# 1LD-20-mk-1_0_0.net
KiCad netlist of a schematic drawn in EAGLE
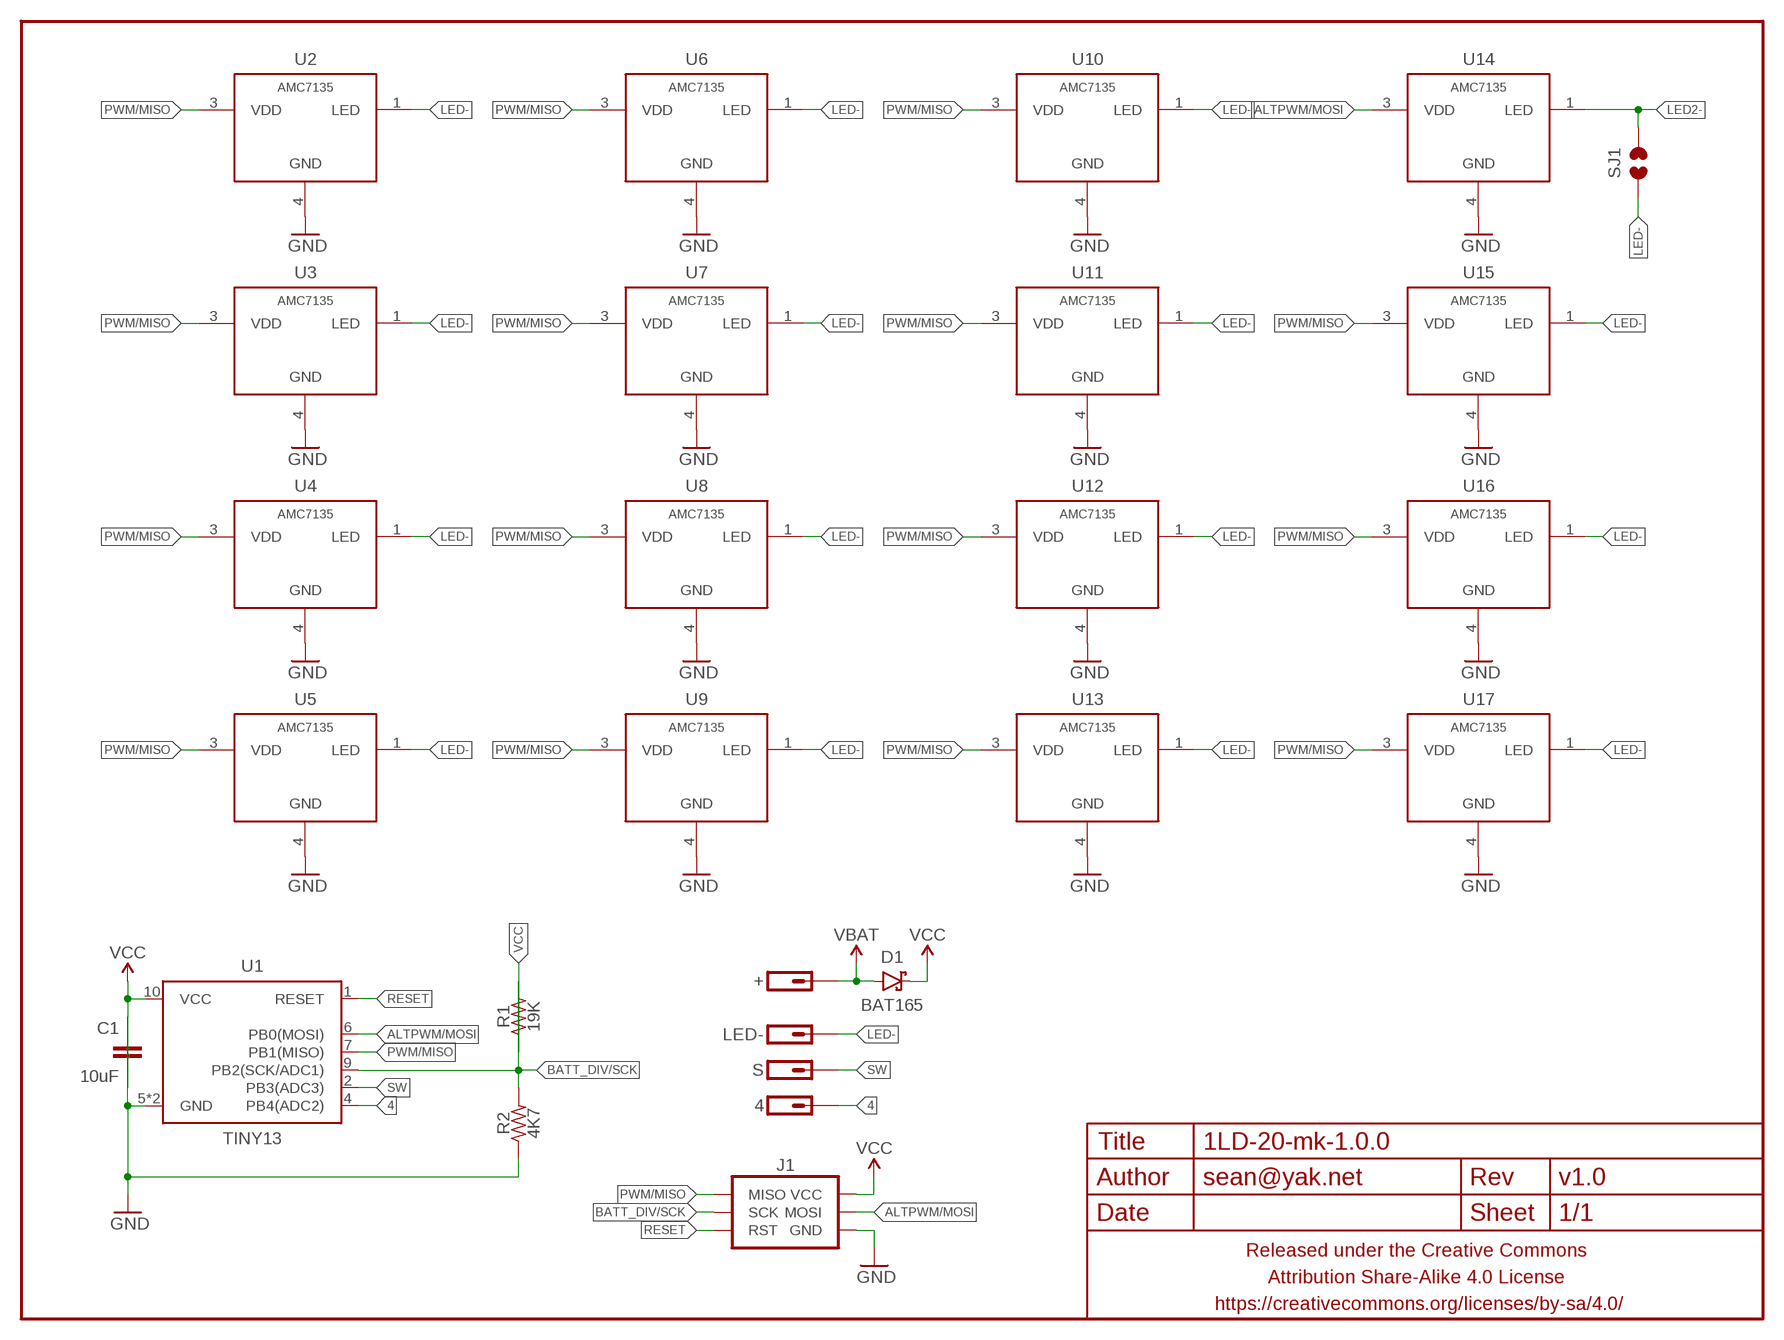
[diagram p0: schematic, sheet 1]

(export (version "E")
  (design (tool "Eeschema 10.0.6"))
  (components
    (comp (ref "+")
      (value "M01PTH-1.3MM-NARROWISH")
      (footprint "eagle-import:1X01-1.3MM-CIR-NARROW-NS")
      (libsource (lib "eagle-import") (part "M01PTH-1.3MM-NARROWISH"))
    )
    (comp (ref "4")
      (value "M01SMD-1MM-DIA-NS")
      (footprint "eagle-import:1X01-SMD-1MM-DIA-NS")
      (libsource (lib "eagle-import") (part "M01SMD-1MM-DIA-NS"))
    )
    (comp (ref "C1")
      (value "10uF")
      (footprint "eagle-import:C0402")
      (libsource (lib "eagle-import") (part "CAPACITOR-CERAMICC0402"))
    )
    (comp (ref "D1")
      (value "BAT165")
      (footprint "eagle-import:SOD323-SCHOTTKY")
      (libsource (lib "eagle-import") (part "DIODE-SCHOTTKYSOD323"))
    )
    (comp (ref "FRAME1")
      (value "FRAME-LETTERNO_PACKAGE")
      (footprint "eagle-import:DUMMY")
      (fields
        (field (name "DESIGNER") "Nobody")
        (field (name "VERSION") "v01")
        (field (name "DESIGNER_1") "sean@yak.net")
        (field (name "VERSION_1") "v1.0")
      )
      (libsource (lib "eagle-import") (part "FRAME-LETTERNO_PACKAGE"))
    )
    (comp (ref "J1")
      (value "AVR_SPI_PRG_6SMD-1.27MM")
      (footprint "eagle-import:2X3-1.27MM-SMD")
      (libsource (lib "eagle-import") (part "AVR_SPI_PRG_6SMD-1.27MM"))
    )
    (comp (ref "LED-")
      (value "M01PTH-1MM-CIR-NS")
      (footprint "eagle-import:1X01-1MM-CIR-NS")
      (libsource (lib "eagle-import") (part "M01PTH-1MM-CIR-NS"))
    )
    (comp (ref "R1")
      (value "19K")
      (footprint "eagle-import:R0402")
      (libsource (lib "eagle-import") (part "RESISTORR0402"))
    )
    (comp (ref "R2")
      (value "4K7")
      (footprint "eagle-import:R0402")
      (libsource (lib "eagle-import") (part "RESISTORR0402"))
    )
    (comp (ref "S")
      (value "M01SMD-1MM-DIA-NS")
      (footprint "eagle-import:1X01-SMD-1MM-DIA-NS")
      (libsource (lib "eagle-import") (part "M01SMD-1MM-DIA-NS"))
    )
    (comp (ref "SJ1")
      (value "JUMPER-PAD-2-NOSMOL_NS")
      (footprint "eagle-import:PAD-JUMPER-2-NO_SMOL_NS")
      (libsource (lib "eagle-import") (part "JUMPER-PAD-2-NOSMOL_NS"))
    )
    (comp (ref "U1")
      (value "TINY13")
      (footprint "eagle-import:QFN10(2X5)")
      (libsource (lib "eagle-import") (part "ATTINY1310M1"))
    )
    (comp (ref "U2")
      (value "AMC7135")
      (footprint "eagle-import:SOT89-NOTHERM-ROUNDED-LESS")
      (libsource (lib "eagle-import") (part "AMC7135ROUNDED-LESS"))
    )
    (comp (ref "U3")
      (value "AMC7135")
      (footprint "eagle-import:SOT89-NOTHERM-ROUNDED-LESS")
      (libsource (lib "eagle-import") (part "AMC7135ROUNDED-LESS"))
    )
    (comp (ref "U4")
      (value "AMC7135")
      (footprint "eagle-import:SOT89-NOTHERM-ROUNDED-LESS")
      (libsource (lib "eagle-import") (part "AMC7135ROUNDED-LESS"))
    )
    (comp (ref "U5")
      (value "AMC7135")
      (footprint "eagle-import:SOT89-NOTHERM-ROUNDED-LESS")
      (libsource (lib "eagle-import") (part "AMC7135ROUNDED-LESS"))
    )
    (comp (ref "U6")
      (value "AMC7135")
      (footprint "eagle-import:SOT89-NOTHERM-ROUNDED-LESS")
      (libsource (lib "eagle-import") (part "AMC7135ROUNDED-LESS"))
    )
    (comp (ref "U7")
      (value "AMC7135")
      (footprint "eagle-import:SOT89-NOTHERM-ROUNDED-LESS")
      (libsource (lib "eagle-import") (part "AMC7135ROUNDED-LESS"))
    )
    (comp (ref "U8")
      (value "AMC7135")
      (footprint "eagle-import:SOT89-NOTHERM-ROUNDED-LESS")
      (libsource (lib "eagle-import") (part "AMC7135ROUNDED-LESS"))
    )
    (comp (ref "U9")
      (value "AMC7135")
      (footprint "eagle-import:SOT89-NOTHERM-ROUNDED-LESS")
      (libsource (lib "eagle-import") (part "AMC7135ROUNDED-LESS"))
    )
    (comp (ref "U10")
      (value "AMC7135")
      (footprint "eagle-import:SOT89-NOTHERM-ROUNDED-LESS")
      (libsource (lib "eagle-import") (part "AMC7135ROUNDED-LESS"))
    )
    (comp (ref "U11")
      (value "AMC7135")
      (footprint "eagle-import:SOT89-NOTHERM-ROUNDED-LESS")
      (libsource (lib "eagle-import") (part "AMC7135ROUNDED-LESS"))
    )
    (comp (ref "U12")
      (value "AMC7135")
      (footprint "eagle-import:SOT89-NOTHERM-ROUNDED-LESS")
      (libsource (lib "eagle-import") (part "AMC7135ROUNDED-LESS"))
    )
    (comp (ref "U13")
      (value "AMC7135")
      (footprint "eagle-import:SOT89-NOTHERM-ROUNDED-LESS")
      (libsource (lib "eagle-import") (part "AMC7135ROUNDED-LESS"))
    )
    (comp (ref "U14")
      (value "AMC7135")
      (footprint "eagle-import:SOT89-NOTHERM-ROUNDED-LESS")
      (libsource (lib "eagle-import") (part "AMC7135ROUNDED-LESS"))
    )
    (comp (ref "U15")
      (value "AMC7135")
      (footprint "eagle-import:SOT89-NOTHERM-ROUNDED-LESS")
      (libsource (lib "eagle-import") (part "AMC7135ROUNDED-LESS"))
    )
    (comp (ref "U16")
      (value "AMC7135")
      (footprint "eagle-import:SOT89-NOTHERM-ROUNDED-LESS")
      (libsource (lib "eagle-import") (part "AMC7135ROUNDED-LESS"))
    )
    (comp (ref "U17")
      (value "AMC7135")
      (footprint "eagle-import:SOT89-NOTHERM-ROUNDED-LESS")
      (libsource (lib "eagle-import") (part "AMC7135ROUNDED-LESS"))
    )
  )
  (nets
    (net (code "1") (name "4") (class "Default")
      (node (ref "4") (pin "P$1") (pinfunction "1_P$1") (pintype "passive"))
      (node (ref "U1") (pin "4") (pinfunction "PB4(ADC2)_4") (pintype "bidirectional"))
    )
    (net (code "2") (name "ALTPWM{slash}MOSI") (class "Default")
      (node (ref "J1") (pin "4") (pinfunction "MOSI_4") (pintype "passive"))
      (node (ref "U1") (pin "6") (pinfunction "PB0(MOSI)_6") (pintype "bidirectional"))
      (node (ref "U14") (pin "3") (pinfunction "VDD_3") (pintype "bidirectional"))
    )
    (net (code "3") (name "BATT_DIV{slash}SCK") (class "Default")
      (node (ref "J1") (pin "3") (pinfunction "SCK_3") (pintype "passive"))
      (node (ref "R1") (pin "2") (pinfunction "2_2") (pintype "passive"))
      (node (ref "R2") (pin "2") (pinfunction "2_2") (pintype "passive"))
      (node (ref "U1") (pin "9") (pinfunction "PB2(SCK/ADC1)_9") (pintype "bidirectional"))
    )
    (net (code "4") (name "GND") (class "Default")
      (node (ref "C1") (pin "1") (pinfunction "1_1") (pintype "passive"))
      (node (ref "J1") (pin "6") (pinfunction "GND_6") (pintype "passive"))
      (node (ref "R2") (pin "1") (pinfunction "1_1") (pintype "passive"))
      (node (ref "U1") (pin "5") (pinfunction "GND_5") (pintype "bidirectional"))
      (node (ref "U1") (pin "PAD") (pinfunction "GND_PAD") (pintype "bidirectional"))
      (node (ref "U10") (pin "4") (pinfunction "GND_4") (pintype "bidirectional"))
      (node (ref "U11") (pin "4") (pinfunction "GND_4") (pintype "bidirectional"))
      (node (ref "U12") (pin "4") (pinfunction "GND_4") (pintype "bidirectional"))
      (node (ref "U13") (pin "4") (pinfunction "GND_4") (pintype "bidirectional"))
      (node (ref "U14") (pin "4") (pinfunction "GND_4") (pintype "bidirectional"))
      (node (ref "U15") (pin "4") (pinfunction "GND_4") (pintype "bidirectional"))
      (node (ref "U16") (pin "4") (pinfunction "GND_4") (pintype "bidirectional"))
      (node (ref "U17") (pin "4") (pinfunction "GND_4") (pintype "bidirectional"))
      (node (ref "U2") (pin "4") (pinfunction "GND_4") (pintype "bidirectional"))
      (node (ref "U3") (pin "4") (pinfunction "GND_4") (pintype "bidirectional"))
      (node (ref "U4") (pin "4") (pinfunction "GND_4") (pintype "bidirectional"))
      (node (ref "U5") (pin "4") (pinfunction "GND_4") (pintype "bidirectional"))
      (node (ref "U6") (pin "4") (pinfunction "GND_4") (pintype "bidirectional"))
      (node (ref "U7") (pin "4") (pinfunction "GND_4") (pintype "bidirectional"))
      (node (ref "U8") (pin "4") (pinfunction "GND_4") (pintype "bidirectional"))
      (node (ref "U9") (pin "4") (pinfunction "GND_4") (pintype "bidirectional"))
    )
    (net (code "5") (name "LED-") (class "Default")
      (node (ref "LED-") (pin "1") (pinfunction "1_1") (pintype "passive"))
      (node (ref "SJ1") (pin "1") (pinfunction "1_1") (pintype "passive"))
      (node (ref "U10") (pin "1") (pinfunction "LED_1") (pintype "bidirectional"))
      (node (ref "U11") (pin "1") (pinfunction "LED_1") (pintype "bidirectional"))
      (node (ref "U12") (pin "1") (pinfunction "LED_1") (pintype "bidirectional"))
      (node (ref "U13") (pin "1") (pinfunction "LED_1") (pintype "bidirectional"))
      (node (ref "U15") (pin "1") (pinfunction "LED_1") (pintype "bidirectional"))
      (node (ref "U16") (pin "1") (pinfunction "LED_1") (pintype "bidirectional"))
      (node (ref "U17") (pin "1") (pinfunction "LED_1") (pintype "bidirectional"))
      (node (ref "U2") (pin "1") (pinfunction "LED_1") (pintype "bidirectional"))
      (node (ref "U3") (pin "1") (pinfunction "LED_1") (pintype "bidirectional"))
      (node (ref "U4") (pin "1") (pinfunction "LED_1") (pintype "bidirectional"))
      (node (ref "U5") (pin "1") (pinfunction "LED_1") (pintype "bidirectional"))
      (node (ref "U6") (pin "1") (pinfunction "LED_1") (pintype "bidirectional"))
      (node (ref "U7") (pin "1") (pinfunction "LED_1") (pintype "bidirectional"))
      (node (ref "U8") (pin "1") (pinfunction "LED_1") (pintype "bidirectional"))
      (node (ref "U9") (pin "1") (pinfunction "LED_1") (pintype "bidirectional"))
    )
    (net (code "6") (name "LED2-") (class "Default")
      (node (ref "SJ1") (pin "2") (pinfunction "2_2") (pintype "passive"))
      (node (ref "U14") (pin "1") (pinfunction "LED_1") (pintype "bidirectional"))
    )
    (net (code "7") (name "PWM{slash}MISO") (class "Default")
      (node (ref "J1") (pin "1") (pinfunction "MISO_1") (pintype "passive"))
      (node (ref "U1") (pin "7") (pinfunction "PB1(MISO)_7") (pintype "bidirectional"))
      (node (ref "U10") (pin "3") (pinfunction "VDD_3") (pintype "bidirectional"))
      (node (ref "U11") (pin "3") (pinfunction "VDD_3") (pintype "bidirectional"))
      (node (ref "U12") (pin "3") (pinfunction "VDD_3") (pintype "bidirectional"))
      (node (ref "U13") (pin "3") (pinfunction "VDD_3") (pintype "bidirectional"))
      (node (ref "U15") (pin "3") (pinfunction "VDD_3") (pintype "bidirectional"))
      (node (ref "U16") (pin "3") (pinfunction "VDD_3") (pintype "bidirectional"))
      (node (ref "U17") (pin "3") (pinfunction "VDD_3") (pintype "bidirectional"))
      (node (ref "U2") (pin "3") (pinfunction "VDD_3") (pintype "bidirectional"))
      (node (ref "U3") (pin "3") (pinfunction "VDD_3") (pintype "bidirectional"))
      (node (ref "U4") (pin "3") (pinfunction "VDD_3") (pintype "bidirectional"))
      (node (ref "U5") (pin "3") (pinfunction "VDD_3") (pintype "bidirectional"))
      (node (ref "U6") (pin "3") (pinfunction "VDD_3") (pintype "bidirectional"))
      (node (ref "U7") (pin "3") (pinfunction "VDD_3") (pintype "bidirectional"))
      (node (ref "U8") (pin "3") (pinfunction "VDD_3") (pintype "bidirectional"))
      (node (ref "U9") (pin "3") (pinfunction "VDD_3") (pintype "bidirectional"))
    )
    (net (code "8") (name "RESET") (class "Default")
      (node (ref "J1") (pin "5") (pinfunction "RST_5") (pintype "passive"))
      (node (ref "U1") (pin "1") (pinfunction "RESET_1") (pintype "bidirectional"))
    )
    (net (code "9") (name "SW") (class "Default")
      (node (ref "S") (pin "P$1") (pinfunction "1_P$1") (pintype "passive"))
      (node (ref "U1") (pin "2") (pinfunction "PB3(ADC3)_2") (pintype "bidirectional"))
    )
    (net (code "10") (name "VBAT") (class "Default")
      (node (ref "+") (pin "P$1") (pinfunction "1_P$1") (pintype "passive"))
      (node (ref "D1") (pin "A") (pinfunction "A_A") (pintype "passive"))
    )
    (net (code "11") (name "VCC") (class "Default")
      (node (ref "C1") (pin "2") (pinfunction "2_2") (pintype "passive"))
      (node (ref "D1") (pin "C") (pinfunction "C_C") (pintype "passive"))
      (node (ref "J1") (pin "2") (pinfunction "VCC_2") (pintype "passive"))
      (node (ref "R1") (pin "1") (pinfunction "1_1") (pintype "passive"))
      (node (ref "U1") (pin "10") (pinfunction "VCC_10") (pintype "bidirectional"))
    )
  )
)
